# 2-CPU_POWER.net
KiCad netlist of a schematic drawn in Altium Designer
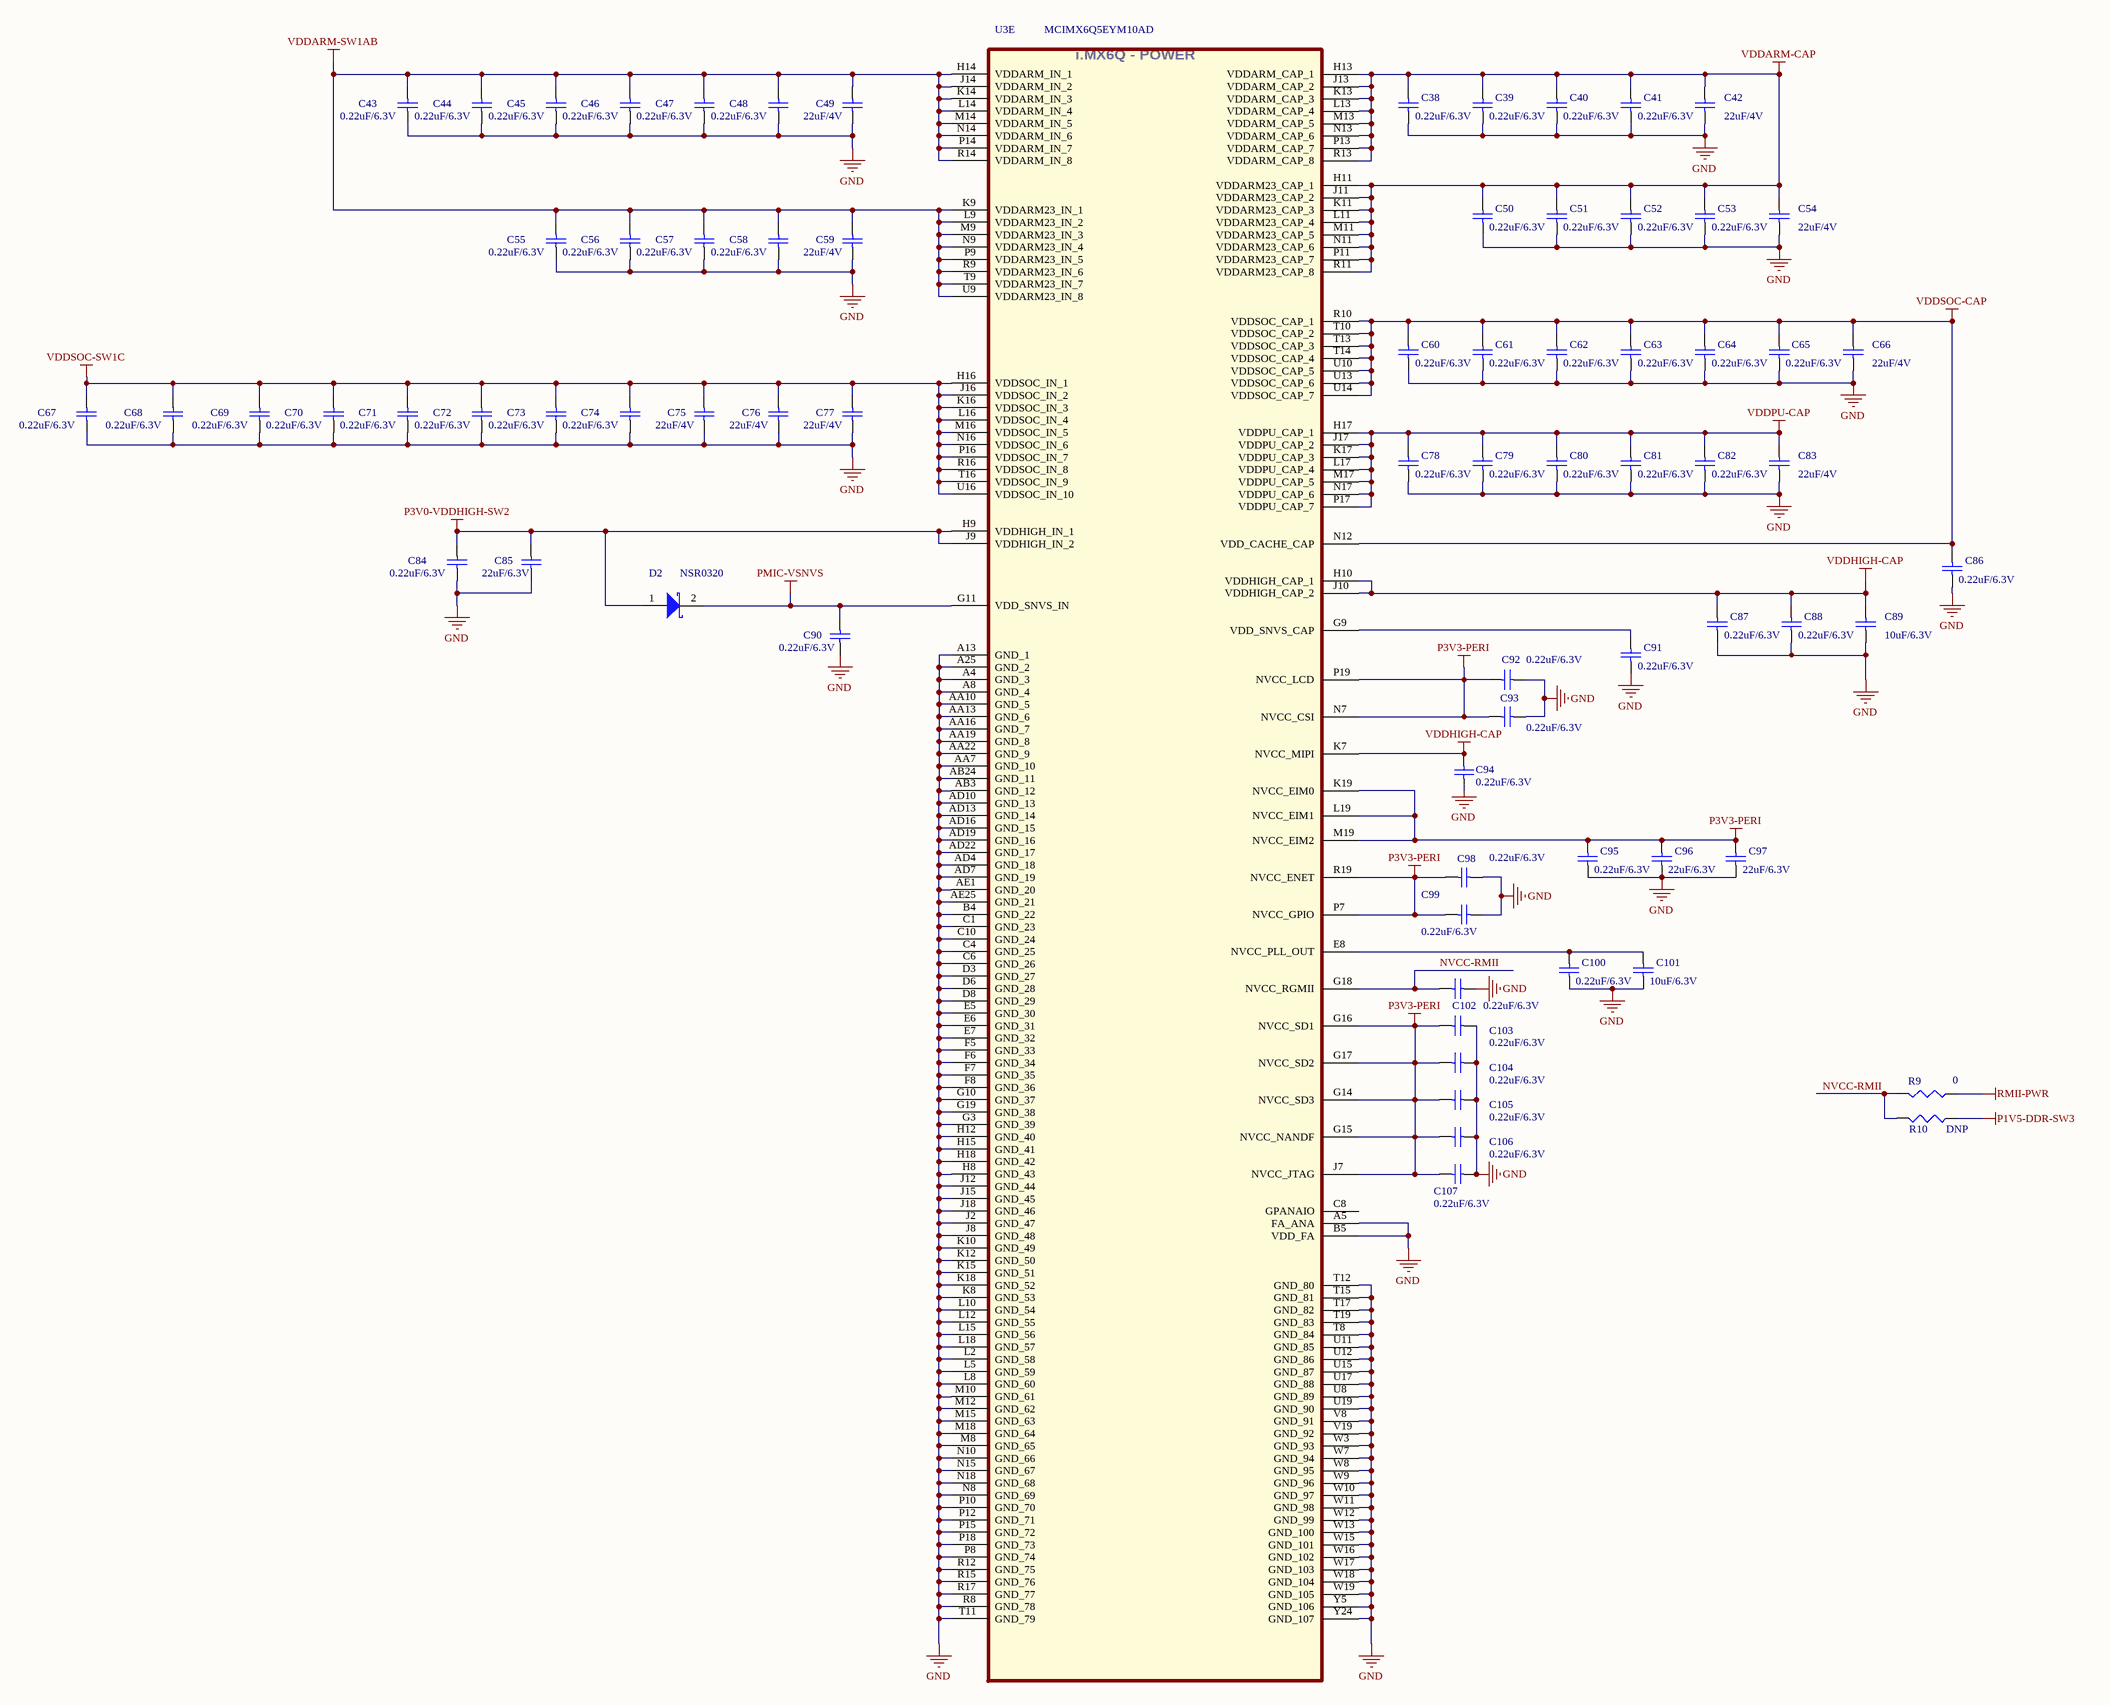
[diagram p0: 2-CPU_POWER.SchDoc]

(export (version "E")
  (design (tool "Eeschema 10.0.6"))
  (components
    (comp (ref "C38")
      (value "0.22uF/6.3V")
      (footprint "0201_CC")
      (description "Capacitor")
      (fields (field (name "PUBLISHER") "Altium Limited"))
      (libsource (lib "Miscellaneous Devices") (part "Cap"))
    )
    (comp (ref "C39")
      (value "0.22uF/6.3V")
      (footprint "0201_CC")
      (description "Capacitor")
      (fields (field (name "PUBLISHER") "Altium Limited"))
      (libsource (lib "Miscellaneous Devices") (part "Cap"))
    )
    (comp (ref "C40")
      (value "0.22uF/6.3V")
      (footprint "0201_CC")
      (description "Capacitor")
      (fields (field (name "PUBLISHER") "Altium Limited"))
      (libsource (lib "Miscellaneous Devices") (part "Cap"))
    )
    (comp (ref "C41")
      (value "0.22uF/6.3V")
      (footprint "0201_CC")
      (description "Capacitor")
      (fields (field (name "PUBLISHER") "Altium Limited"))
      (libsource (lib "Miscellaneous Devices") (part "Cap"))
    )
    (comp (ref "C42")
      (value "22uF/4V")
      (footprint "0603_CC")
      (description "Capacitor")
      (fields (field (name "PUBLISHER") "Altium Limited"))
      (libsource (lib "Miscellaneous Devices") (part "Cap"))
    )
    (comp (ref "C43")
      (value "0.22uF/6.3V")
      (footprint "0201_CC")
      (description "Capacitor")
      (fields (field (name "PUBLISHER") "Altium Limited"))
      (libsource (lib "Miscellaneous Devices") (part "Cap"))
    )
    (comp (ref "C44")
      (value "0.22uF/6.3V")
      (footprint "0201_CC")
      (description "Capacitor")
      (fields (field (name "PUBLISHER") "Altium Limited"))
      (libsource (lib "Miscellaneous Devices") (part "Cap"))
    )
    (comp (ref "C45")
      (value "0.22uF/6.3V")
      (footprint "0201_CC")
      (description "Capacitor")
      (fields (field (name "PUBLISHER") "Altium Limited"))
      (libsource (lib "Miscellaneous Devices") (part "Cap"))
    )
    (comp (ref "C46")
      (value "0.22uF/6.3V")
      (footprint "0201_CC")
      (description "Capacitor")
      (fields (field (name "PUBLISHER") "Altium Limited"))
      (libsource (lib "Miscellaneous Devices") (part "Cap"))
    )
    (comp (ref "C47")
      (value "0.22uF/6.3V")
      (footprint "0201_CC")
      (description "Capacitor")
      (fields (field (name "PUBLISHER") "Altium Limited"))
      (libsource (lib "Miscellaneous Devices") (part "Cap"))
    )
    (comp (ref "C48")
      (value "0.22uF/6.3V")
      (footprint "0201_CC")
      (description "Capacitor")
      (fields (field (name "PUBLISHER") "Altium Limited"))
      (libsource (lib "Miscellaneous Devices") (part "Cap"))
    )
    (comp (ref "C49")
      (value "22uF/4V")
      (footprint "0603_CC")
      (description "Capacitor")
      (fields (field (name "PUBLISHER") "Altium Limited"))
      (libsource (lib "Miscellaneous Devices") (part "Cap"))
    )
    (comp (ref "C50")
      (value "0.22uF/6.3V")
      (footprint "0201_CC")
      (description "Capacitor")
      (fields (field (name "PUBLISHER") "Altium Limited"))
      (libsource (lib "Miscellaneous Devices") (part "Cap"))
    )
    (comp (ref "C51")
      (value "0.22uF/6.3V")
      (footprint "0201_CC")
      (description "Capacitor")
      (fields (field (name "PUBLISHER") "Altium Limited"))
      (libsource (lib "Miscellaneous Devices") (part "Cap"))
    )
    (comp (ref "C52")
      (value "0.22uF/6.3V")
      (footprint "0201_CC")
      (description "Capacitor")
      (fields (field (name "PUBLISHER") "Altium Limited"))
      (libsource (lib "Miscellaneous Devices") (part "Cap"))
    )
    (comp (ref "C53")
      (value "0.22uF/6.3V")
      (footprint "0201_CC")
      (description "Capacitor")
      (fields (field (name "PUBLISHER") "Altium Limited"))
      (libsource (lib "Miscellaneous Devices") (part "Cap"))
    )
    (comp (ref "C54")
      (value "22uF/4V")
      (footprint "0603_CC")
      (description "Capacitor")
      (fields (field (name "PUBLISHER") "Altium Limited"))
      (libsource (lib "Miscellaneous Devices") (part "Cap"))
    )
    (comp (ref "C55")
      (value "0.22uF/6.3V")
      (footprint "0201_CC")
      (description "Capacitor")
      (fields (field (name "PUBLISHER") "Altium Limited"))
      (libsource (lib "Miscellaneous Devices") (part "Cap"))
    )
    (comp (ref "C56")
      (value "0.22uF/6.3V")
      (footprint "0201_CC")
      (description "Capacitor")
      (fields (field (name "PUBLISHER") "Altium Limited"))
      (libsource (lib "Miscellaneous Devices") (part "Cap"))
    )
    (comp (ref "C57")
      (value "0.22uF/6.3V")
      (footprint "0201_CC")
      (description "Capacitor")
      (fields (field (name "PUBLISHER") "Altium Limited"))
      (libsource (lib "Miscellaneous Devices") (part "Cap"))
    )
    (comp (ref "C58")
      (value "0.22uF/6.3V")
      (footprint "0201_CC")
      (description "Capacitor")
      (fields (field (name "PUBLISHER") "Altium Limited"))
      (libsource (lib "Miscellaneous Devices") (part "Cap"))
    )
    (comp (ref "C59")
      (value "22uF/4V")
      (footprint "0603_CC")
      (description "Capacitor")
      (fields (field (name "PUBLISHER") "Altium Limited"))
      (libsource (lib "Miscellaneous Devices") (part "Cap"))
    )
    (comp (ref "C60")
      (value "0.22uF/6.3V")
      (footprint "0201_CC")
      (description "Capacitor")
      (fields (field (name "PUBLISHER") "Altium Limited"))
      (libsource (lib "Miscellaneous Devices") (part "Cap"))
    )
    (comp (ref "C61")
      (value "0.22uF/6.3V")
      (footprint "0201_CC")
      (description "Capacitor")
      (fields (field (name "PUBLISHER") "Altium Limited"))
      (libsource (lib "Miscellaneous Devices") (part "Cap"))
    )
    (comp (ref "C62")
      (value "0.22uF/6.3V")
      (footprint "0201_CC")
      (description "Capacitor")
      (fields (field (name "PUBLISHER") "Altium Limited"))
      (libsource (lib "Miscellaneous Devices") (part "Cap"))
    )
    (comp (ref "C63")
      (value "0.22uF/6.3V")
      (footprint "0201_CC")
      (description "Capacitor")
      (fields (field (name "PUBLISHER") "Altium Limited"))
      (libsource (lib "Miscellaneous Devices") (part "Cap"))
    )
    (comp (ref "C64")
      (value "0.22uF/6.3V")
      (footprint "0201_CC")
      (description "Capacitor")
      (fields (field (name "PUBLISHER") "Altium Limited"))
      (libsource (lib "Miscellaneous Devices") (part "Cap"))
    )
    (comp (ref "C65")
      (value "0.22uF/6.3V")
      (footprint "0201_CC")
      (description "Capacitor")
      (fields (field (name "PUBLISHER") "Altium Limited"))
      (libsource (lib "Miscellaneous Devices") (part "Cap"))
    )
    (comp (ref "C66")
      (value "22uF/4V")
      (footprint "0603_CC")
      (description "Capacitor")
      (fields (field (name "PUBLISHER") "Altium Limited"))
      (libsource (lib "Miscellaneous Devices") (part "Cap"))
    )
    (comp (ref "C67")
      (value "0.22uF/6.3V")
      (footprint "0201_CC")
      (description "Capacitor")
      (fields (field (name "PUBLISHER") "Altium Limited"))
      (libsource (lib "Miscellaneous Devices") (part "Cap"))
    )
    (comp (ref "C68")
      (value "0.22uF/6.3V")
      (footprint "0201_CC")
      (description "Capacitor")
      (fields (field (name "PUBLISHER") "Altium Limited"))
      (libsource (lib "Miscellaneous Devices") (part "Cap"))
    )
    (comp (ref "C69")
      (value "0.22uF/6.3V")
      (footprint "0201_CC")
      (description "Capacitor")
      (fields (field (name "PUBLISHER") "Altium Limited"))
      (libsource (lib "Miscellaneous Devices") (part "Cap"))
    )
    (comp (ref "C70")
      (value "0.22uF/6.3V")
      (footprint "0201_CC")
      (description "Capacitor")
      (fields (field (name "PUBLISHER") "Altium Limited"))
      (libsource (lib "Miscellaneous Devices") (part "Cap"))
    )
    (comp (ref "C71")
      (value "0.22uF/6.3V")
      (footprint "0201_CC")
      (description "Capacitor")
      (fields (field (name "PUBLISHER") "Altium Limited"))
      (libsource (lib "Miscellaneous Devices") (part "Cap"))
    )
    (comp (ref "C72")
      (value "0.22uF/6.3V")
      (footprint "0201_CC")
      (description "Capacitor")
      (fields (field (name "PUBLISHER") "Altium Limited"))
      (libsource (lib "Miscellaneous Devices") (part "Cap"))
    )
    (comp (ref "C73")
      (value "0.22uF/6.3V")
      (footprint "0201_CC")
      (description "Capacitor")
      (fields (field (name "PUBLISHER") "Altium Limited"))
      (libsource (lib "Miscellaneous Devices") (part "Cap"))
    )
    (comp (ref "C74")
      (value "0.22uF/6.3V")
      (footprint "0201_CC")
      (description "Capacitor")
      (fields (field (name "PUBLISHER") "Altium Limited"))
      (libsource (lib "Miscellaneous Devices") (part "Cap"))
    )
    (comp (ref "C75")
      (value "22uF/4V")
      (footprint "0603_CC")
      (description "Capacitor")
      (fields (field (name "PUBLISHER") "Altium Limited"))
      (libsource (lib "Miscellaneous Devices") (part "Cap"))
    )
    (comp (ref "C76")
      (value "22uF/4V")
      (footprint "0603_CC")
      (description "Capacitor")
      (fields (field (name "PUBLISHER") "Altium Limited"))
      (libsource (lib "Miscellaneous Devices") (part "Cap"))
    )
    (comp (ref "C77")
      (value "22uF/4V")
      (footprint "0603_CC")
      (description "Capacitor")
      (fields (field (name "PUBLISHER") "Altium Limited"))
      (libsource (lib "Miscellaneous Devices") (part "Cap"))
    )
    (comp (ref "C78")
      (value "0.22uF/6.3V")
      (footprint "0201_CC")
      (description "Capacitor")
      (fields (field (name "PUBLISHER") "Altium Limited"))
      (libsource (lib "Miscellaneous Devices") (part "Cap"))
    )
    (comp (ref "C79")
      (value "0.22uF/6.3V")
      (footprint "0201_CC")
      (description "Capacitor")
      (fields (field (name "PUBLISHER") "Altium Limited"))
      (libsource (lib "Miscellaneous Devices") (part "Cap"))
    )
    (comp (ref "C80")
      (value "0.22uF/6.3V")
      (footprint "0201_CC")
      (description "Capacitor")
      (fields (field (name "PUBLISHER") "Altium Limited"))
      (libsource (lib "Miscellaneous Devices") (part "Cap"))
    )
    (comp (ref "C81")
      (value "0.22uF/6.3V")
      (footprint "0201_CC")
      (description "Capacitor")
      (fields (field (name "PUBLISHER") "Altium Limited"))
      (libsource (lib "Miscellaneous Devices") (part "Cap"))
    )
    (comp (ref "C82")
      (value "0.22uF/6.3V")
      (footprint "0201_CC")
      (description "Capacitor")
      (fields (field (name "PUBLISHER") "Altium Limited"))
      (libsource (lib "Miscellaneous Devices") (part "Cap"))
    )
    (comp (ref "C83")
      (value "22uF/4V")
      (footprint "0603_CC")
      (description "Capacitor")
      (fields (field (name "PUBLISHER") "Altium Limited"))
      (libsource (lib "Miscellaneous Devices") (part "Cap"))
    )
    (comp (ref "C84")
      (value "0.22uF/6.3V")
      (footprint "0201_CC")
      (description "Capacitor")
      (fields (field (name "PUBLISHER") "Altium Limited"))
      (libsource (lib "Miscellaneous Devices") (part "Cap"))
    )
    (comp (ref "C85")
      (value "22uF/6.3V")
      (footprint "0805_CC")
      (description "Capacitor")
      (fields (field (name "PUBLISHER") "Altium Limited"))
      (libsource (lib "Miscellaneous Devices") (part "Cap"))
    )
    (comp (ref "C86")
      (value "0.22uF/6.3V")
      (footprint "0201_CC")
      (description "Capacitor")
      (fields (field (name "PUBLISHER") "Altium Limited"))
      (libsource (lib "Miscellaneous Devices") (part "Cap"))
    )
    (comp (ref "C87")
      (value "0.22uF/6.3V")
      (footprint "0201_CC")
      (description "Capacitor")
      (fields (field (name "PUBLISHER") "Altium Limited"))
      (libsource (lib "Miscellaneous Devices") (part "Cap"))
    )
    (comp (ref "C88")
      (value "0.22uF/6.3V")
      (footprint "0201_CC")
      (description "Capacitor")
      (fields (field (name "PUBLISHER") "Altium Limited"))
      (libsource (lib "Miscellaneous Devices") (part "Cap"))
    )
    (comp (ref "C89")
      (value "10uF/6.3V")
      (footprint "0805_CC")
      (description "Capacitor")
      (fields (field (name "PUBLISHER") "Altium Limited"))
      (libsource (lib "Miscellaneous Devices") (part "Cap"))
    )
    (comp (ref "C90")
      (value "0.22uF/6.3V")
      (footprint "0201_CC")
      (description "Capacitor")
      (fields (field (name "PUBLISHER") "Altium Limited"))
      (libsource (lib "Miscellaneous Devices") (part "Cap"))
    )
    (comp (ref "C91")
      (value "0.22uF/6.3V")
      (footprint "0201_CC")
      (description "Capacitor")
      (fields (field (name "PUBLISHER") "Altium Limited"))
      (libsource (lib "Miscellaneous Devices") (part "Cap"))
    )
    (comp (ref "C92")
      (value "0.22uF/6.3V")
      (footprint "0201_CC")
      (description "Capacitor")
      (fields (field (name "PUBLISHER") "Altium Limited"))
      (libsource (lib "Miscellaneous Devices") (part "Cap"))
    )
    (comp (ref "C93")
      (value "0.22uF/6.3V")
      (footprint "0201_CC")
      (description "Capacitor")
      (fields (field (name "PUBLISHER") "Altium Limited"))
      (libsource (lib "Miscellaneous Devices") (part "Cap"))
    )
    (comp (ref "C94")
      (value "0.22uF/6.3V")
      (footprint "0201_CC")
      (description "Capacitor")
      (fields (field (name "PUBLISHER") "Altium Limited"))
      (libsource (lib "Miscellaneous Devices") (part "Cap"))
    )
    (comp (ref "C95")
      (value "0.22uF/6.3V")
      (footprint "0201_CC")
      (description "Capacitor")
      (fields (field (name "PUBLISHER") "Altium Limited"))
      (libsource (lib "Miscellaneous Devices") (part "Cap"))
    )
    (comp (ref "C96")
      (value "22uF/6.3V")
      (footprint "0805_CC")
      (description "Capacitor")
      (fields (field (name "PUBLISHER") "Altium Limited"))
      (libsource (lib "Miscellaneous Devices") (part "Cap"))
    )
    (comp (ref "C97")
      (value "22uF/6.3V")
      (footprint "0805_CC")
      (description "Capacitor")
      (fields (field (name "PUBLISHER") "Altium Limited"))
      (libsource (lib "Miscellaneous Devices") (part "Cap"))
    )
    (comp (ref "C98")
      (value "0.22uF/6.3V")
      (footprint "0201_CC")
      (description "Capacitor")
      (fields (field (name "PUBLISHER") "Altium Limited"))
      (libsource (lib "Miscellaneous Devices") (part "Cap"))
    )
    (comp (ref "C99")
      (value "0.22uF/6.3V")
      (footprint "0201_CC")
      (description "Capacitor")
      (fields (field (name "PUBLISHER") "Altium Limited"))
      (libsource (lib "Miscellaneous Devices") (part "Cap"))
    )
    (comp (ref "C100")
      (value "0.22uF/6.3V")
      (footprint "0201_CC")
      (description "Capacitor")
      (fields (field (name "PUBLISHER") "Altium Limited"))
      (libsource (lib "Miscellaneous Devices") (part "Cap"))
    )
    (comp (ref "C101")
      (value "10uF/6.3V")
      (footprint "0805_CC")
      (description "Capacitor")
      (fields (field (name "PUBLISHER") "Altium Limited"))
      (libsource (lib "Miscellaneous Devices") (part "Cap"))
    )
    (comp (ref "C102")
      (value "0.22uF/6.3V")
      (footprint "0201_CC")
      (description "Capacitor")
      (fields (field (name "PUBLISHER") "Altium Limited"))
      (libsource (lib "Miscellaneous Devices") (part "Cap"))
    )
    (comp (ref "C103")
      (value "0.22uF/6.3V")
      (footprint "0201_CC")
      (description "Capacitor")
      (fields (field (name "PUBLISHER") "Altium Limited"))
      (libsource (lib "Miscellaneous Devices") (part "Cap"))
    )
    (comp (ref "C104")
      (value "0.22uF/6.3V")
      (footprint "0201_CC")
      (description "Capacitor")
      (fields (field (name "PUBLISHER") "Altium Limited"))
      (libsource (lib "Miscellaneous Devices") (part "Cap"))
    )
    (comp (ref "C105")
      (value "0.22uF/6.3V")
      (footprint "0201_CC")
      (description "Capacitor")
      (fields (field (name "PUBLISHER") "Altium Limited"))
      (libsource (lib "Miscellaneous Devices") (part "Cap"))
    )
    (comp (ref "C106")
      (value "0.22uF/6.3V")
      (footprint "0201_CC")
      (description "Capacitor")
      (fields (field (name "PUBLISHER") "Altium Limited"))
      (libsource (lib "Miscellaneous Devices") (part "Cap"))
    )
    (comp (ref "C107")
      (value "0.22uF/6.3V")
      (footprint "0201_CC")
      (description "Capacitor")
      (fields (field (name "PUBLISHER") "Altium Limited"))
      (libsource (lib "Miscellaneous Devices") (part "Cap"))
    )
    (comp (ref "D2")
      (value "NSR0320")
      (footprint "SOD323")
      (description "Schottky Rectifier")
      (libsource (lib "Miscellaneous Devices") (part "Diode 11DQ03"))
    )
    (comp (ref "R9")
      (value "0")
      (footprint "0603_CC")
      (description "Resistor")
      (fields (field (name "PUBLISHER") "Altium Limited"))
      (libsource (lib "Miscellaneous Devices") (part "Res3"))
    )
    (comp (ref "R10")
      (value "DNP")
      (footprint "0603_CC")
      (description "Resistor")
      (fields (field (name "PUBLISHER") "Altium Limited"))
      (libsource (lib "Miscellaneous Devices") (part "Res3"))
    )
    (comp (ref "U3")
      (value "MCIMX6Q5EYM10AD")
      (footprint "FCPBGA")
      (description "IC MCU MX6QUAD ARM CORTEX-A9 FCPBGA624")
      (libsource (lib "*") (part "PCIMX6Q6VV1A"))
    )
  )
  (nets
    (net (code "1") (name "/NVCC-RMII") (class "Default")
      (node (ref "C102") (pin "1") (pinfunction "1_1") (pintype "passive"))
      (node (ref "R10") (pin "2") (pinfunction "2_2") (pintype "passive"))
      (node (ref "R9") (pin "2") (pinfunction "2_2") (pintype "passive"))
      (node (ref "U3") (pin "G18") (pinfunction "NVCC_RGMII_G18") (pintype "power_in"))
    )
    (net (code "2") (name "GND") (class "Default")
      (node (ref "C100") (pin "2") (pinfunction "2_2") (pintype "passive"))
      (node (ref "C101") (pin "2") (pinfunction "2_2") (pintype "passive"))
      (node (ref "C102") (pin "2") (pinfunction "2_2") (pintype "passive"))
      (node (ref "C103") (pin "2") (pinfunction "2_2") (pintype "passive"))
      (node (ref "C104") (pin "2") (pinfunction "2_2") (pintype "passive"))
      (node (ref "C105") (pin "2") (pinfunction "2_2") (pintype "passive"))
      (node (ref "C106") (pin "2") (pinfunction "2_2") (pintype "passive"))
      (node (ref "C107") (pin "2") (pinfunction "2_2") (pintype "passive"))
      (node (ref "C38") (pin "2") (pinfunction "2_2") (pintype "passive"))
      (node (ref "C39") (pin "2") (pinfunction "2_2") (pintype "passive"))
      (node (ref "C40") (pin "2") (pinfunction "2_2") (pintype "passive"))
      (node (ref "C41") (pin "2") (pinfunction "2_2") (pintype "passive"))
      (node (ref "C42") (pin "2") (pinfunction "2_2") (pintype "passive"))
      (node (ref "C43") (pin "2") (pinfunction "2_2") (pintype "passive"))
      (node (ref "C44") (pin "2") (pinfunction "2_2") (pintype "passive"))
      (node (ref "C45") (pin "2") (pinfunction "2_2") (pintype "passive"))
      (node (ref "C46") (pin "2") (pinfunction "2_2") (pintype "passive"))
      (node (ref "C47") (pin "2") (pinfunction "2_2") (pintype "passive"))
      (node (ref "C48") (pin "2") (pinfunction "2_2") (pintype "passive"))
      (node (ref "C49") (pin "2") (pinfunction "2_2") (pintype "passive"))
      (node (ref "C50") (pin "2") (pinfunction "2_2") (pintype "passive"))
      (node (ref "C51") (pin "2") (pinfunction "2_2") (pintype "passive"))
      (node (ref "C52") (pin "2") (pinfunction "2_2") (pintype "passive"))
      (node (ref "C53") (pin "2") (pinfunction "2_2") (pintype "passive"))
      (node (ref "C54") (pin "2") (pinfunction "2_2") (pintype "passive"))
      (node (ref "C55") (pin "2") (pinfunction "2_2") (pintype "passive"))
      (node (ref "C56") (pin "2") (pinfunction "2_2") (pintype "passive"))
      (node (ref "C57") (pin "2") (pinfunction "2_2") (pintype "passive"))
      (node (ref "C58") (pin "2") (pinfunction "2_2") (pintype "passive"))
      (node (ref "C59") (pin "2") (pinfunction "2_2") (pintype "passive"))
      (node (ref "C60") (pin "2") (pinfunction "2_2") (pintype "passive"))
      (node (ref "C61") (pin "2") (pinfunction "2_2") (pintype "passive"))
      (node (ref "C62") (pin "2") (pinfunction "2_2") (pintype "passive"))
      (node (ref "C63") (pin "2") (pinfunction "2_2") (pintype "passive"))
      (node (ref "C64") (pin "2") (pinfunction "2_2") (pintype "passive"))
      (node (ref "C65") (pin "2") (pinfunction "2_2") (pintype "passive"))
      (node (ref "C66") (pin "2") (pinfunction "2_2") (pintype "passive"))
      (node (ref "C67") (pin "2") (pinfunction "2_2") (pintype "passive"))
      (node (ref "C68") (pin "2") (pinfunction "2_2") (pintype "passive"))
      (node (ref "C69") (pin "2") (pinfunction "2_2") (pintype "passive"))
      (node (ref "C70") (pin "2") (pinfunction "2_2") (pintype "passive"))
      (node (ref "C71") (pin "2") (pinfunction "2_2") (pintype "passive"))
      (node (ref "C72") (pin "2") (pinfunction "2_2") (pintype "passive"))
      (node (ref "C73") (pin "2") (pinfunction "2_2") (pintype "passive"))
      (node (ref "C74") (pin "2") (pinfunction "2_2") (pintype "passive"))
      (node (ref "C75") (pin "2") (pinfunction "2_2") (pintype "passive"))
      (node (ref "C76") (pin "2") (pinfunction "2_2") (pintype "passive"))
      (node (ref "C77") (pin "2") (pinfunction "2_2") (pintype "passive"))
      (node (ref "C78") (pin "2") (pinfunction "2_2") (pintype "passive"))
      (node (ref "C79") (pin "2") (pinfunction "2_2") (pintype "passive"))
      (node (ref "C80") (pin "2") (pinfunction "2_2") (pintype "passive"))
      (node (ref "C81") (pin "2") (pinfunction "2_2") (pintype "passive"))
      (node (ref "C82") (pin "2") (pinfunction "2_2") (pintype "passive"))
      (node (ref "C83") (pin "2") (pinfunction "2_2") (pintype "passive"))
      (node (ref "C84") (pin "2") (pinfunction "2_2") (pintype "passive"))
      (node (ref "C85") (pin "2") (pinfunction "2_2") (pintype "passive"))
      (node (ref "C86") (pin "2") (pinfunction "2_2") (pintype "passive"))
      (node (ref "C87") (pin "2") (pinfunction "2_2") (pintype "passive"))
      (node (ref "C88") (pin "2") (pinfunction "2_2") (pintype "passive"))
      (node (ref "C89") (pin "2") (pinfunction "2_2") (pintype "passive"))
      (node (ref "C90") (pin "2") (pinfunction "2_2") (pintype "passive"))
      (node (ref "C91") (pin "2") (pinfunction "2_2") (pintype "passive"))
      (node (ref "C92") (pin "2") (pinfunction "2_2") (pintype "passive"))
      (node (ref "C93") (pin "2") (pinfunction "2_2") (pintype "passive"))
      (node (ref "C94") (pin "1") (pinfunction "1_1") (pintype "passive"))
      (node (ref "C95") (pin "2") (pinfunction "2_2") (pintype "passive"))
      (node (ref "C96") (pin "2") (pinfunction "2_2") (pintype "passive"))
      (node (ref "C97") (pin "2") (pinfunction "2_2") (pintype "passive"))
      (node (ref "C98") (pin "2") (pinfunction "2_2") (pintype "passive"))
      (node (ref "C99") (pin "2") (pinfunction "2_2") (pintype "passive"))
      (node (ref "U3") (pin "A13") (pinfunction "GND_1_A13") (pintype "power_in"))
      (node (ref "U3") (pin "A25") (pinfunction "GND_2_A25") (pintype "power_in"))
      (node (ref "U3") (pin "A4") (pinfunction "GND_3_A4") (pintype "power_in"))
      (node (ref "U3") (pin "A5") (pinfunction "FA_ANA_A5") (pintype "power_in"))
      (node (ref "U3") (pin "A8") (pinfunction "GND_4_A8") (pintype "power_in"))
      (node (ref "U3") (pin "AA10") (pinfunction "GND_5_AA10") (pintype "power_in"))
      (node (ref "U3") (pin "AA13") (pinfunction "GND_6_AA13") (pintype "power_in"))
      (node (ref "U3") (pin "AA16") (pinfunction "GND_7_AA16") (pintype "power_in"))
      (node (ref "U3") (pin "AA19") (pinfunction "GND_8_AA19") (pintype "power_in"))
      (node (ref "U3") (pin "AA22") (pinfunction "GND_9_AA22") (pintype "power_in"))
      (node (ref "U3") (pin "AA7") (pinfunction "GND_10_AA7") (pintype "power_in"))
      (node (ref "U3") (pin "AB24") (pinfunction "GND_11_AB24") (pintype "power_in"))
      (node (ref "U3") (pin "AB3") (pinfunction "GND_12_AB3") (pintype "power_in"))
      (node (ref "U3") (pin "AD10") (pinfunction "GND_13_AD10") (pintype "power_in"))
      (node (ref "U3") (pin "AD13") (pinfunction "GND_14_AD13") (pintype "power_in"))
      (node (ref "U3") (pin "AD16") (pinfunction "GND_15_AD16") (pintype "power_in"))
      (node (ref "U3") (pin "AD19") (pinfunction "GND_16_AD19") (pintype "power_in"))
      (node (ref "U3") (pin "AD22") (pinfunction "GND_17_AD22") (pintype "power_in"))
      (node (ref "U3") (pin "AD4") (pinfunction "GND_18_AD4") (pintype "power_in"))
      (node (ref "U3") (pin "AD7") (pinfunction "GND_19_AD7") (pintype "power_in"))
      (node (ref "U3") (pin "AE1") (pinfunction "GND_20_AE1") (pintype "power_in"))
      (node (ref "U3") (pin "AE25") (pinfunction "GND_21_AE25") (pintype "power_in"))
      (node (ref "U3") (pin "B4") (pinfunction "GND_22_B4") (pintype "power_in"))
      (node (ref "U3") (pin "B5") (pinfunction "VDD_FA_B5") (pintype "power_in"))
      (node (ref "U3") (pin "C1") (pinfunction "GND_23_C1") (pintype "power_in"))
      (node (ref "U3") (pin "C10") (pinfunction "GND_24_C10") (pintype "power_in"))
      (node (ref "U3") (pin "C4") (pinfunction "GND_25_C4") (pintype "power_in"))
      (node (ref "U3") (pin "C6") (pinfunction "GND_26_C6") (pintype "power_in"))
      (node (ref "U3") (pin "D3") (pinfunction "GND_27_D3") (pintype "power_in"))
      (node (ref "U3") (pin "D6") (pinfunction "GND_28_D6") (pintype "power_in"))
      (node (ref "U3") (pin "D8") (pinfunction "GND_29_D8") (pintype "power_in"))
      (node (ref "U3") (pin "E5") (pinfunction "GND_30_E5") (pintype "power_in"))
      (node (ref "U3") (pin "E6") (pinfunction "GND_31_E6") (pintype "power_in"))
      (node (ref "U3") (pin "E7") (pinfunction "GND_32_E7") (pintype "power_in"))
      (node (ref "U3") (pin "F5") (pinfunction "GND_33_F5") (pintype "power_in"))
      (node (ref "U3") (pin "F6") (pinfunction "GND_34_F6") (pintype "power_in"))
      (node (ref "U3") (pin "F7") (pinfunction "GND_35_F7") (pintype "power_in"))
      (node (ref "U3") (pin "F8") (pinfunction "GND_36_F8") (pintype "power_in"))
      (node (ref "U3") (pin "G10") (pinfunction "GND_37_G10") (pintype "power_in"))
      (node (ref "U3") (pin "G19") (pinfunction "GND_38_G19") (pintype "power_in"))
      (node (ref "U3") (pin "G3") (pinfunction "GND_39_G3") (pintype "power_in"))
      (node (ref "U3") (pin "H12") (pinfunction "GND_40_H12") (pintype "power_in"))
      (node (ref "U3") (pin "H15") (pinfunction "GND_41_H15") (pintype "power_in"))
      (node (ref "U3") (pin "H18") (pinfunction "GND_42_H18") (pintype "power_in"))
      (node (ref "U3") (pin "H8") (pinfunction "GND_43_H8") (pintype "power_in"))
      (node (ref "U3") (pin "J12") (pinfunction "GND_44_J12") (pintype "power_in"))
      (node (ref "U3") (pin "J15") (pinfunction "GND_45_J15") (pintype "power_in"))
      (node (ref "U3") (pin "J18") (pinfunction "GND_46_J18") (pintype "power_in"))
      (node (ref "U3") (pin "J2") (pinfunction "GND_47_J2") (pintype "power_in"))
      (node (ref "U3") (pin "J8") (pinfunction "GND_48_J8") (pintype "power_in"))
      (node (ref "U3") (pin "K10") (pinfunction "GND_49_K10") (pintype "power_in"))
      (node (ref "U3") (pin "K12") (pinfunction "GND_50_K12") (pintype "power_in"))
      (node (ref "U3") (pin "K15") (pinfunction "GND_51_K15") (pintype "power_in"))
      (node (ref "U3") (pin "K18") (pinfunction "GND_52_K18") (pintype "power_in"))
      (node (ref "U3") (pin "K8") (pinfunction "GND_53_K8") (pintype "power_in"))
      (node (ref "U3") (pin "L10") (pinfunction "GND_54_L10") (pintype "power_in"))
      (node (ref "U3") (pin "L12") (pinfunction "GND_55_L12") (pintype "power_in"))
      (node (ref "U3") (pin "L15") (pinfunction "GND_56_L15") (pintype "power_in"))
      (node (ref "U3") (pin "L18") (pinfunction "GND_57_L18") (pintype "power_in"))
      (node (ref "U3") (pin "L2") (pinfunction "GND_58_L2") (pintype "power_in"))
      (node (ref "U3") (pin "L5") (pinfunction "GND_59_L5") (pintype "power_in"))
      (node (ref "U3") (pin "L8") (pinfunction "GND_60_L8") (pintype "power_in"))
      (node (ref "U3") (pin "M10") (pinfunction "GND_61_M10") (pintype "power_in"))
      (node (ref "U3") (pin "M12") (pinfunction "GND_62_M12") (pintype "power_in"))
      (node (ref "U3") (pin "M15") (pinfunction "GND_63_M15") (pintype "power_in"))
      (node (ref "U3") (pin "M18") (pinfunction "GND_64_M18") (pintype "power_in"))
      (node (ref "U3") (pin "M8") (pinfunction "GND_65_M8") (pintype "power_in"))
      (node (ref "U3") (pin "N10") (pinfunction "GND_66_N10") (pintype "power_in"))
      (node (ref "U3") (pin "N15") (pinfunction "GND_67_N15") (pintype "power_in"))
      (node (ref "U3") (pin "N18") (pinfunction "GND_68_N18") (pintype "power_in"))
      (node (ref "U3") (pin "N8") (pinfunction "GND_69_N8") (pintype "power_in"))
      (node (ref "U3") (pin "P10") (pinfunction "GND_70_P10") (pintype "power_in"))
      (node (ref "U3") (pin "P12") (pinfunction "GND_71_P12") (pintype "power_in"))
      (node (ref "U3") (pin "P15") (pinfunction "GND_72_P15") (pintype "power_in"))
      (node (ref "U3") (pin "P18") (pinfunction "GND_73_P18") (pintype "power_in"))
      (node (ref "U3") (pin "P8") (pinfunction "GND_74_P8") (pintype "power_in"))
      (node (ref "U3") (pin "R12") (pinfunction "GND_75_R12") (pintype "power_in"))
      (node (ref "U3") (pin "R15") (pinfunction "GND_76_R15") (pintype "power_in"))
      (node (ref "U3") (pin "R17") (pinfunction "GND_77_R17") (pintype "power_in"))
      (node (ref "U3") (pin "R8") (pinfunction "GND_78_R8") (pintype "power_in"))
      (node (ref "U3") (pin "T11") (pinfunction "GND_79_T11") (pintype "power_in"))
      (node (ref "U3") (pin "T12") (pinfunction "GND_80_T12") (pintype "power_in"))
      (node (ref "U3") (pin "T15") (pinfunction "GND_81_T15") (pintype "power_in"))
      (node (ref "U3") (pin "T17") (pinfunction "GND_82_T17") (pintype "power_in"))
      (node (ref "U3") (pin "T19") (pinfunction "GND_83_T19") (pintype "power_in"))
      (node (ref "U3") (pin "T8") (pinfunction "GND_84_T8") (pintype "power_in"))
      (node (ref "U3") (pin "U11") (pinfunction "GND_85_U11") (pintype "power_in"))
      (node (ref "U3") (pin "U12") (pinfunction "GND_86_U12") (pintype "power_in"))
      (node (ref "U3") (pin "U15") (pinfunction "GND_87_U15") (pintype "power_in"))
      (node (ref "U3") (pin "U17") (pinfunction "GND_88_U17") (pintype "power_in"))
      (node (ref "U3") (pin "U19") (pinfunction "GND_90_U19") (pintype "power_in"))
      (node (ref "U3") (pin "U8") (pinfunction "GND_89_U8") (pintype "power_in"))
      (node (ref "U3") (pin "V19") (pinfunction "GND_92_V19") (pintype "power_in"))
      (node (ref "U3") (pin "V8") (pinfunction "GND_91_V8") (pintype "power_in"))
      (node (ref "U3") (pin "W10") (pinfunction "GND_97_W10") (pintype "power_in"))
      (node (ref "U3") (pin "W11") (pinfunction "GND_98_W11") (pintype "power_in"))
      (node (ref "U3") (pin "W12") (pinfunction "GND_99_W12") (pintype "power_in"))
      (node (ref "U3") (pin "W13") (pinfunction "GND_100_W13") (pintype "power_in"))
      (node (ref "U3") (pin "W15") (pinfunction "GND_101_W15") (pintype "power_in"))
      (node (ref "U3") (pin "W16") (pinfunction "GND_102_W16") (pintype "power_in"))
      (node (ref "U3") (pin "W17") (pinfunction "GND_103_W17") (pintype "power_in"))
      (node (ref "U3") (pin "W18") (pinfunction "GND_104_W18") (pintype "power_in"))
      (node (ref "U3") (pin "W19") (pinfunction "GND_105_W19") (pintype "power_in"))
      (node (ref "U3") (pin "W3") (pinfunction "GND_93_W3") (pintype "power_in"))
      (node (ref "U3") (pin "W7") (pinfunction "GND_94_W7") (pintype "power_in"))
      (node (ref "U3") (pin "W8") (pinfunction "GND_95_W8") (pintype "power_in"))
      (node (ref "U3") (pin "W9") (pinfunction "GND_96_W9") (pintype "power_in"))
      (node (ref "U3") (pin "Y24") (pinfunction "GND_107_Y24") (pintype "power_in"))
      (node (ref "U3") (pin "Y5") (pinfunction "GND_106_Y5") (pintype "power_in"))
    )
    (net (code "3") (name "Net-(U3E-NVCC_PLL_OUT)") (class "Default")
      (node (ref "C100") (pin "1") (pinfunction "1_1") (pintype "passive"))
      (node (ref "C101") (pin "1") (pinfunction "1_1") (pintype "passive"))
      (node (ref "U3") (pin "E8") (pinfunction "NVCC_PLL_OUT_E8") (pintype "power_in"))
    )
    (net (code "4") (name "Net-(U3E-VDD_SNVS_CAP)") (class "Default")
      (node (ref "C91") (pin "1") (pinfunction "1_1") (pintype "passive"))
      (node (ref "U3") (pin "G9") (pinfunction "VDD_SNVS_CAP_G9") (pintype "power_in"))
    )
    (net (code "5") (name "P1V5-DDR-SW3") (class "Default")
      (node (ref "R10") (pin "1") (pinfunction "1_1") (pintype "passive"))
    )
    (net (code "6") (name "P3V0-VDDHIGH-SW2") (class "Default")
      (node (ref "C84") (pin "1") (pinfunction "1_1") (pintype "passive"))
      (node (ref "C85") (pin "1") (pinfunction "1_1") (pintype "passive"))
      (node (ref "D2") (pin "1") (pinfunction "A_1") (pintype "passive"))
      (node (ref "U3") (pin "H9") (pinfunction "VDDHIGH_IN_1_H9") (pintype "power_in"))
      (node (ref "U3") (pin "J9") (pinfunction "VDDHIGH_IN_2_J9") (pintype "power_in"))
    )
    (net (code "7") (name "P3V3-PERI") (class "Default")
      (node (ref "C103") (pin "1") (pinfunction "1_1") (pintype "passive"))
      (node (ref "C104") (pin "1") (pinfunction "1_1") (pintype "passive"))
      (node (ref "C105") (pin "1") (pinfunction "1_1") (pintype "passive"))
      (node (ref "C106") (pin "1") (pinfunction "1_1") (pintype "passive"))
      (node (ref "C107") (pin "1") (pinfunction "1_1") (pintype "passive"))
      (node (ref "C92") (pin "1") (pinfunction "1_1") (pintype "passive"))
      (node (ref "C93") (pin "1") (pinfunction "1_1") (pintype "passive"))
      (node (ref "C95") (pin "1") (pinfunction "1_1") (pintype "passive"))
      (node (ref "C96") (pin "1") (pinfunction "1_1") (pintype "passive"))
      (node (ref "C97") (pin "1") (pinfunction "1_1") (pintype "passive"))
      (node (ref "C98") (pin "1") (pinfunction "1_1") (pintype "passive"))
      (node (ref "C99") (pin "1") (pinfunction "1_1") (pintype "passive"))
      (node (ref "U3") (pin "G14") (pinfunction "NVCC_SD3_G14") (pintype "power_in"))
      (node (ref "U3") (pin "G15") (pinfunction "NVCC_NANDF_G15") (pintype "power_in"))
      (node (ref "U3") (pin "G16") (pinfunction "NVCC_SD1_G16") (pintype "power_in"))
      (node (ref "U3") (pin "G17") (pinfunction "NVCC_SD2_G17") (pintype "power_in"))
      (node (ref "U3") (pin "J7") (pinfunction "NVCC_JTAG_J7") (pintype "power_in"))
      (node (ref "U3") (pin "K19") (pinfunction "NVCC_EIM0_K19") (pintype "power_in"))
      (node (ref "U3") (pin "L19") (pinfunction "NVCC_EIM1_L19") (pintype "power_in"))
      (node (ref "U3") (pin "M19") (pinfunction "NVCC_EIM2_M19") (pintype "power_in"))
      (node (ref "U3") (pin "N7") (pinfunction "NVCC_CSI_N7") (pintype "power_in"))
      (node (ref "U3") (pin "P19") (pinfunction "NVCC_LCD_P19") (pintype "power_in"))
      (node (ref "U3") (pin "P7") (pinfunction "NVCC_GPIO_P7") (pintype "power_in"))
      (node (ref "U3") (pin "R19") (pinfunction "NVCC_ENET_R19") (pintype "power_in"))
    )
    (net (code "8") (name "PMIC-VSNVS") (class "Default")
      (node (ref "C90") (pin "1") (pinfunction "1_1") (pintype "passive"))
      (node (ref "D2") (pin "2") (pinfunction "K_2") (pintype "passive"))
      (node (ref "U3") (pin "G11") (pinfunction "VDD_SNVS_IN_G11") (pintype "power_in"))
    )
    (net (code "9") (name "RMII-PWR") (class "Default")
      (node (ref "R9") (pin "1") (pinfunction "1_1") (pintype "passive"))
    )
    (net (code "10") (name "VDDARM-CAP") (class "Default")
      (node (ref "C38") (pin "1") (pinfunction "1_1") (pintype "passive"))
      (node (ref "C39") (pin "1") (pinfunction "1_1") (pintype "passive"))
      (node (ref "C40") (pin "1") (pinfunction "1_1") (pintype "passive"))
      (node (ref "C41") (pin "1") (pinfunction "1_1") (pintype "passive"))
      (node (ref "C42") (pin "1") (pinfunction "1_1") (pintype "passive"))
      (node (ref "C50") (pin "1") (pinfunction "1_1") (pintype "passive"))
      (node (ref "C51") (pin "1") (pinfunction "1_1") (pintype "passive"))
      (node (ref "C52") (pin "1") (pinfunction "1_1") (pintype "passive"))
      (node (ref "C53") (pin "1") (pinfunction "1_1") (pintype "passive"))
      (node (ref "C54") (pin "1") (pinfunction "1_1") (pintype "passive"))
      (node (ref "U3") (pin "H11") (pinfunction "VDDARM23_CAP_1_H11") (pintype "power_in"))
      (node (ref "U3") (pin "H13") (pinfunction "VDDARM_CAP_1_H13") (pintype "power_in"))
      (node (ref "U3") (pin "J11") (pinfunction "VDDARM23_CAP_2_J11") (pintype "power_in"))
      (node (ref "U3") (pin "J13") (pinfunction "VDDARM_CAP_2_J13") (pintype "power_in"))
      (node (ref "U3") (pin "K11") (pinfunction "VDDARM23_CAP_3_K11") (pintype "power_in"))
      (node (ref "U3") (pin "K13") (pinfunction "VDDARM_CAP_3_K13") (pintype "power_in"))
      (node (ref "U3") (pin "L11") (pinfunction "VDDARM23_CAP_4_L11") (pintype "power_in"))
      (node (ref "U3") (pin "L13") (pinfunction "VDDARM_CAP_4_L13") (pintype "power_in"))
      (node (ref "U3") (pin "M11") (pinfunction "VDDARM23_CAP_5_M11") (pintype "power_in"))
      (node (ref "U3") (pin "M13") (pinfunction "VDDARM_CAP_5_M13") (pintype "power_in"))
      (node (ref "U3") (pin "N11") (pinfunction "VDDARM23_CAP_6_N11") (pintype "power_in"))
      (node (ref "U3") (pin "N13") (pinfunction "VDDARM_CAP_6_N13") (pintype "power_in"))
      (node (ref "U3") (pin "P11") (pinfunction "VDDARM23_CAP_7_P11") (pintype "power_in"))
      (node (ref "U3") (pin "P13") (pinfunction "VDDARM_CAP_7_P13") (pintype "power_in"))
      (node (ref "U3") (pin "R11") (pinfunction "VDDARM23_CAP_8_R11") (pintype "power_in"))
      (node (ref "U3") (pin "R13") (pinfunction "VDDARM_CAP_8_R13") (pintype "power_in"))
    )
    (net (code "11") (name "VDDARM-SW1AB") (class "Default")
      (node (ref "C43") (pin "1") (pinfunction "1_1") (pintype "passive"))
      (node (ref "C44") (pin "1") (pinfunction "1_1") (pintype "passive"))
      (node (ref "C45") (pin "1") (pinfunction "1_1") (pintype "passive"))
      (node (ref "C46") (pin "1") (pinfunction "1_1") (pintype "passive"))
      (node (ref "C47") (pin "1") (pinfunction "1_1") (pintype "passive"))
      (node (ref "C48") (pin "1") (pinfunction "1_1") (pintype "passive"))
      (node (ref "C49") (pin "1") (pinfunction "1_1") (pintype "passive"))
      (node (ref "C55") (pin "1") (pinfunction "1_1") (pintype "passive"))
      (node (ref "C56") (pin "1") (pinfunction "1_1") (pintype "passive"))
      (node (ref "C57") (pin "1") (pinfunction "1_1") (pintype "passive"))
      (node (ref "C58") (pin "1") (pinfunction "1_1") (pintype "passive"))
      (node (ref "C59") (pin "1") (pinfunction "1_1") (pintype "passive"))
      (node (ref "U3") (pin "H14") (pinfunction "VDDARM_IN_1_H14") (pintype "power_in"))
      (node (ref "U3") (pin "J14") (pinfunction "VDDARM_IN_2_J14") (pintype "power_in"))
      (node (ref "U3") (pin "K14") (pinfunction "VDDARM_IN_3_K14") (pintype "power_in"))
      (node (ref "U3") (pin "K9") (pinfunction "VDDARM23_IN_1_K9") (pintype "power_in"))
      (node (ref "U3") (pin "L14") (pinfunction "VDDARM_IN_4_L14") (pintype "power_in"))
      (node (ref "U3") (pin "L9") (pinfunction "VDDARM23_IN_2_L9") (pintype "power_in"))
      (node (ref "U3") (pin "M14") (pinfunction "VDDARM_IN_5_M14") (pintype "power_in"))
      (node (ref "U3") (pin "M9") (pinfunction "VDDARM23_IN_3_M9") (pintype "power_in"))
      (node (ref "U3") (pin "N14") (pinfunction "VDDARM_IN_6_N14") (pintype "power_in"))
      (node (ref "U3") (pin "N9") (pinfunction "VDDARM23_IN_4_N9") (pintype "power_in"))
      (node (ref "U3") (pin "P14") (pinfunction "VDDARM_IN_7_P14") (pintype "power_in"))
      (node (ref "U3") (pin "P9") (pinfunction "VDDARM23_IN_5_P9") (pintype "power_in"))
      (node (ref "U3") (pin "R14") (pinfunction "VDDARM_IN_8_R14") (pintype "power_in"))
      (node (ref "U3") (pin "R9") (pinfunction "VDDARM23_IN_6_R9") (pintype "power_in"))
      (node (ref "U3") (pin "T9") (pinfunction "VDDARM23_IN_7_T9") (pintype "power_in"))
      (node (ref "U3") (pin "U9") (pinfunction "VDDARM23_IN_8_U9") (pintype "power_in"))
    )
    (net (code "12") (name "VDDHIGH-CAP") (class "Default")
      (node (ref "C87") (pin "1") (pinfunction "1_1") (pintype "passive"))
      (node (ref "C88") (pin "1") (pinfunction "1_1") (pintype "passive"))
      (node (ref "C89") (pin "1") (pinfunction "1_1") (pintype "passive"))
      (node (ref "C94") (pin "2") (pinfunction "2_2") (pintype "passive"))
      (node (ref "U3") (pin "H10") (pinfunction "VDDHIGH_CAP_1_H10") (pintype "power_in"))
      (node (ref "U3") (pin "J10") (pinfunction "VDDHIGH_CAP_2_J10") (pintype "power_in"))
      (node (ref "U3") (pin "K7") (pinfunction "NVCC_MIPI_K7") (pintype "power_in"))
    )
    (net (code "13") (name "VDDPU-CAP") (class "Default")
      (node (ref "C78") (pin "1") (pinfunction "1_1") (pintype "passive"))
      (node (ref "C79") (pin "1") (pinfunction "1_1") (pintype "passive"))
      (node (ref "C80") (pin "1") (pinfunction "1_1") (pintype "passive"))
      (node (ref "C81") (pin "1") (pinfunction "1_1") (pintype "passive"))
      (node (ref "C82") (pin "1") (pinfunction "1_1") (pintype "passive"))
      (node (ref "C83") (pin "1") (pinfunction "1_1") (pintype "passive"))
      (node (ref "U3") (pin "H17") (pinfunction "VDDPU_CAP_1_H17") (pintype "power_in"))
      (node (ref "U3") (pin "J17") (pinfunction "VDDPU_CAP_2_J17") (pintype "power_in"))
      (node (ref "U3") (pin "K17") (pinfunction "VDDPU_CAP_3_K17") (pintype "power_in"))
      (node (ref "U3") (pin "L17") (pinfunction "VDDPU_CAP_4_L17") (pintype "power_in"))
      (node (ref "U3") (pin "M17") (pinfunction "VDDPU_CAP_5_M17") (pintype "power_in"))
      (node (ref "U3") (pin "N17") (pinfunction "VDDPU_CAP_6_N17") (pintype "power_in"))
      (node (ref "U3") (pin "P17") (pinfunction "VDDPU_CAP_7_P17") (pintype "power_in"))
    )
    (net (code "14") (name "VDDSOC-CAP") (class "Default")
      (node (ref "C60") (pin "1") (pinfunction "1_1") (pintype "passive"))
      (node (ref "C61") (pin "1") (pinfunction "1_1") (pintype "passive"))
      (node (ref "C62") (pin "1") (pinfunction "1_1") (pintype "passive"))
      (node (ref "C63") (pin "1") (pinfunction "1_1") (pintype "passive"))
      (node (ref "C64") (pin "1") (pinfunction "1_1") (pintype "passive"))
      (node (ref "C65") (pin "1") (pinfunction "1_1") (pintype "passive"))
      (node (ref "C66") (pin "1") (pinfunction "1_1") (pintype "passive"))
      (node (ref "C86") (pin "1") (pinfunction "1_1") (pintype "passive"))
      (node (ref "U3") (pin "N12") (pinfunction "VDD_CACHE_CAP_N12") (pintype "power_in"))
      (node (ref "U3") (pin "R10") (pinfunction "VDDSOC_CAP_1_R10") (pintype "power_in"))
      (node (ref "U3") (pin "T10") (pinfunction "VDDSOC_CAP_2_T10") (pintype "power_in"))
      (node (ref "U3") (pin "T13") (pinfunction "VDDSOC_CAP_3_T13") (pintype "power_in"))
      (node (ref "U3") (pin "T14") (pinfunction "VDDSOC_CAP_4_T14") (pintype "power_in"))
      (node (ref "U3") (pin "U10") (pinfunction "VDDSOC_CAP_5_U10") (pintype "power_in"))
      (node (ref "U3") (pin "U13") (pinfunction "VDDSOC_CAP_6_U13") (pintype "power_in"))
      (node (ref "U3") (pin "U14") (pinfunction "VDDSOC_CAP_7_U14") (pintype "power_in"))
    )
    (net (code "15") (name "VDDSOC-SW1C") (class "Default")
      (node (ref "C67") (pin "1") (pinfunction "1_1") (pintype "passive"))
      (node (ref "C68") (pin "1") (pinfunction "1_1") (pintype "passive"))
      (node (ref "C69") (pin "1") (pinfunction "1_1") (pintype "passive"))
      (node (ref "C70") (pin "1") (pinfunction "1_1") (pintype "passive"))
      (node (ref "C71") (pin "1") (pinfunction "1_1") (pintype "passive"))
      (node (ref "C72") (pin "1") (pinfunction "1_1") (pintype "passive"))
      (node (ref "C73") (pin "1") (pinfunction "1_1") (pintype "passive"))
      (node (ref "C74") (pin "1") (pinfunction "1_1") (pintype "passive"))
      (node (ref "C75") (pin "1") (pinfunction "1_1") (pintype "passive"))
      (node (ref "C76") (pin "1") (pinfunction "1_1") (pintype "passive"))
      (node (ref "C77") (pin "1") (pinfunction "1_1") (pintype "passive"))
      (node (ref "U3") (pin "H16") (pinfunction "VDDSOC_IN_1_H16") (pintype "power_in"))
      (node (ref "U3") (pin "J16") (pinfunction "VDDSOC_IN_2_J16") (pintype "power_in"))
      (node (ref "U3") (pin "K16") (pinfunction "VDDSOC_IN_3_K16") (pintype "power_in"))
      (node (ref "U3") (pin "L16") (pinfunction "VDDSOC_IN_4_L16") (pintype "power_in"))
      (node (ref "U3") (pin "M16") (pinfunction "VDDSOC_IN_5_M16") (pintype "power_in"))
      (node (ref "U3") (pin "N16") (pinfunction "VDDSOC_IN_6_N16") (pintype "power_in"))
      (node (ref "U3") (pin "P16") (pinfunction "VDDSOC_IN_7_P16") (pintype "power_in"))
      (node (ref "U3") (pin "R16") (pinfunction "VDDSOC_IN_8_R16") (pintype "power_in"))
      (node (ref "U3") (pin "T16") (pinfunction "VDDSOC_IN_9_T16") (pintype "power_in"))
      (node (ref "U3") (pin "U16") (pinfunction "VDDSOC_IN_10_U16") (pintype "power_in"))
    )
    (net (code "16") (name "unconnected-(U3E-GPANAIO-PadC8)") (class "Default")
      (node (ref "U3") (pin "C8") (pinfunction "GPANAIO_C8") (pintype "power_in"))
    )
  )
)
